# Struct.net
KiCad netlist of a schematic drawn in Altium Designer
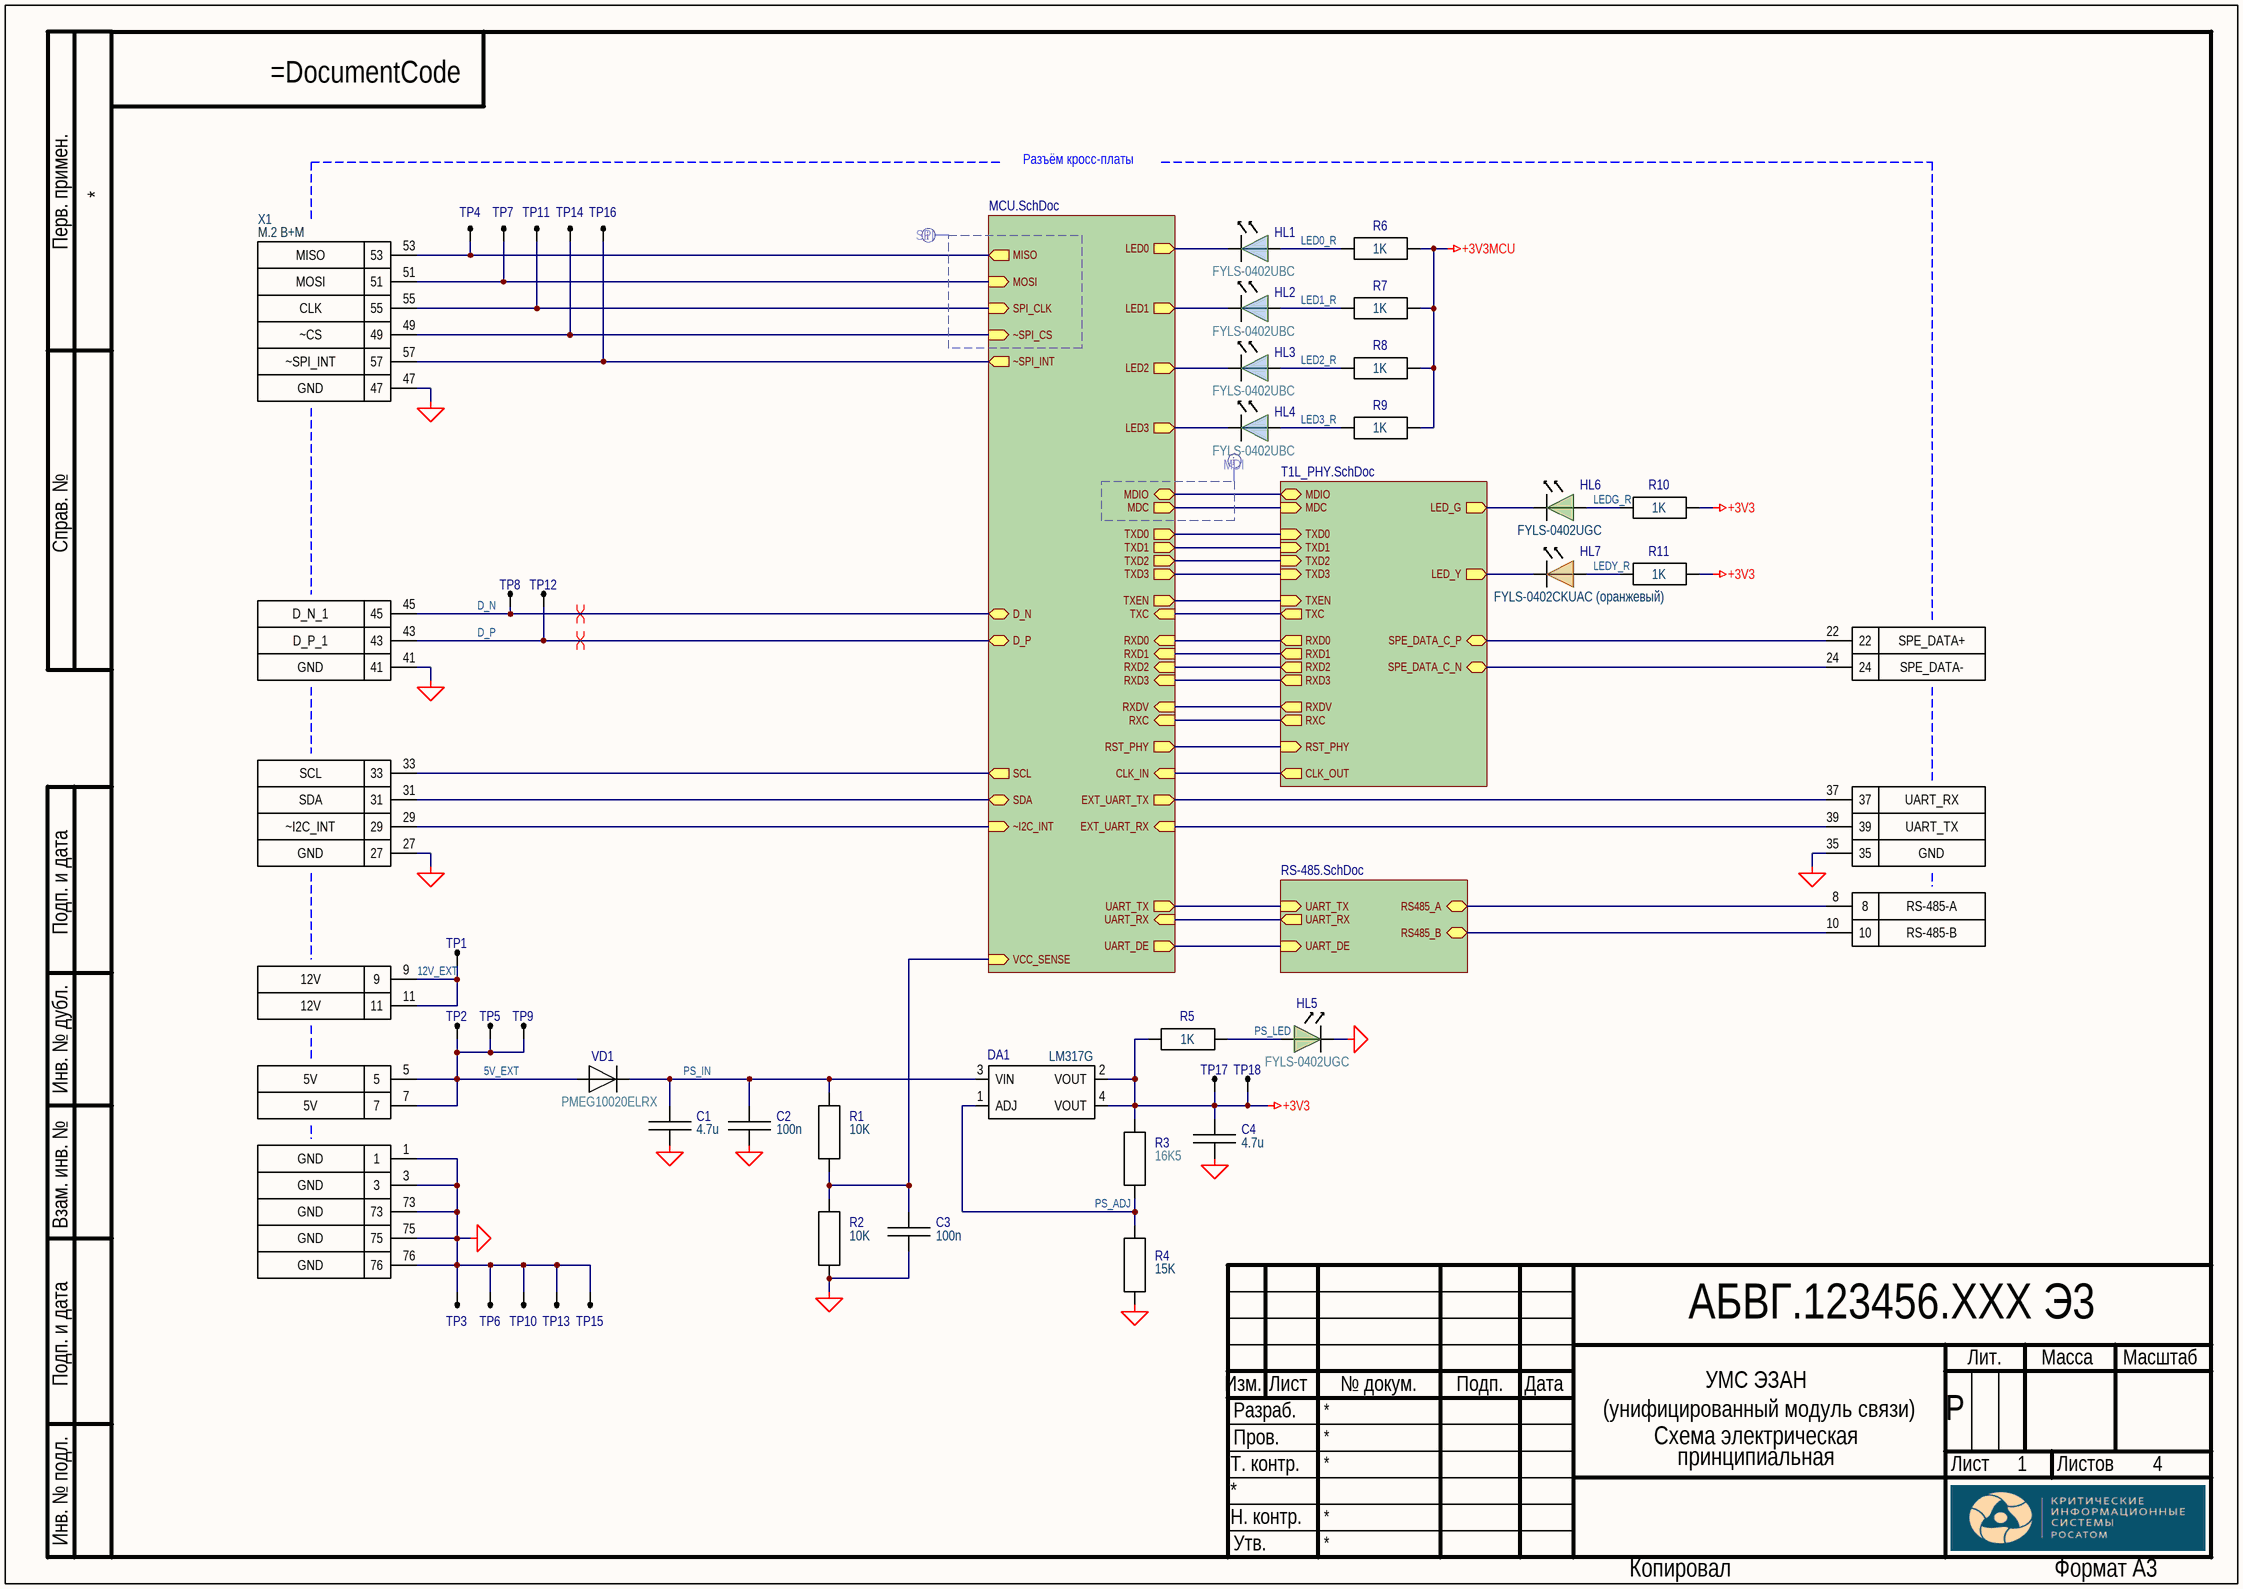
[diagram p0: Struct.SchDoc]

(export (version "E")
  (design (tool "Eeschema 10.0.6"))
  (components
    (comp (ref "C1")
      (value "4.7u")
      (footprint "C0603")
      (description "Чип-конденсатор 4,7 мкФ 10% 16 В X5R 0603")
      (fields
        (field (name "MANUFACTURER PART NUMBER") "CC0603KRX5R7BB475")
        (field (name "MANUFACTURER") "Yageo")
      )
      (libsource (lib "ums") (part "C0603"))
    )
    (comp (ref "C2")
      (value "100n")
      (footprint "C0402")
      (description "Чип-конденсатор 100 нФ 10% 50 В X7R 0402")
      (fields
        (field (name "MANUFACTURER PART NUMBER") "CC0402KRX7R9BB104")
        (field (name "MANUFACTURER") "Yageo")
      )
      (libsource (lib "ums") (part "C0402"))
    )
    (comp (ref "C3")
      (value "100n")
      (footprint "C0402")
      (description "Чип-конденсатор 100 нФ 10% 50 В X7R 0402")
      (fields
        (field (name "MANUFACTURER PART NUMBER") "CC0402KRX7R9BB104")
        (field (name "MANUFACTURER") "Yageo")
      )
      (libsource (lib "ums") (part "C0402"))
    )
    (comp (ref "C4")
      (value "4.7u")
      (footprint "C0603")
      (description "Чип-конденсатор 4,7 мкФ 10% 16 В X5R 0603")
      (fields
        (field (name "MANUFACTURER PART NUMBER") "CC0603KRX5R7BB475")
        (field (name "MANUFACTURER") "Yageo")
      )
      (libsource (lib "ums") (part "C0603"))
    )
    (comp (ref "DA1")
      (value "LM317G")
      (footprint "SOT-223")
      (description "LDO-регулятор SOT-223")
      (fields (field (name "MANUFACTURER") "UMW"))
      (libsource (lib "mconv_fnr_eval_v1") (part "LM317G"))
    )
    (comp (ref "HL1")
      (value "FYLS-0402UBC")
      (footprint "LED_SMD_0402_blue")
      (description "Светодиод SMD 0402 прямой синий FYLS-0402UBC")
      (fields (field (name "MANUFACTURER") "Foryard"))
      (libsource (lib "ums") (part "FYLS-0402UBC"))
    )
    (comp (ref "HL2")
      (value "FYLS-0402UBC")
      (footprint "LED_SMD_0402_blue")
      (description "Светодиод SMD 0402 прямой синий FYLS-0402UBC")
      (fields (field (name "MANUFACTURER") "Foryard"))
      (libsource (lib "ums") (part "FYLS-0402UBC"))
    )
    (comp (ref "HL3")
      (value "FYLS-0402UBC")
      (footprint "LED_SMD_0402_blue")
      (description "Светодиод SMD 0402 прямой синий FYLS-0402UBC")
      (fields (field (name "MANUFACTURER") "Foryard"))
      (libsource (lib "ums") (part "FYLS-0402UBC"))
    )
    (comp (ref "HL4")
      (value "FYLS-0402UBC")
      (footprint "LED_SMD_0402_blue")
      (description "Светодиод SMD 0402 прямой синий FYLS-0402UBC")
      (fields (field (name "MANUFACTURER") "Foryard"))
      (libsource (lib "ums") (part "FYLS-0402UBC"))
    )
    (comp (ref "HL5")
      (value "FYLS-0402UGC")
      (footprint "LED_SMD_0402")
      (description "Светодиод SMD 0402 прямой зелёный FYLS-0402UGC")
      (fields (field (name "MANUFACTURER") "Foryard"))
      (libsource (lib "ums") (part "FYLS-0402UGC"))
    )
    (comp (ref "HL6")
      (value "FYLS-0402UGC")
      (footprint "LED_SMD_0402")
      (description "Светодиод SMD 0402 прямой зелёный FYLS-0402UGC")
      (fields (field (name "MANUFACTURER") "Foryard"))
      (libsource (lib "ums") (part "FYLS-0402UGC"))
    )
    (comp (ref "HL7")
      (value "FYLS-0402CKUAC (оранжевый)")
      (footprint "LED_SMD_0402_orange")
      (description "Светодиод SMD 0402 прямой оранжевый 0402")
      (fields
        (field (name "MANUFACTURER PART NUMBER") "FYLS-0402CKUAC")
        (field (name "MANUFACTURER") "Foryard")
      )
      (libsource (lib "ums") (part "FYLS-0402CKUAC"))
    )
    (comp (ref "R1")
      (value "10K")
      (footprint "R0402")
      (description "Чип-резистор 10 кОм 1% 0402")
      (fields
        (field (name "MANUFACTURER PART NUMBER") "RC0402FR-0710KL")
        (field (name "MANUFACTURER") "Yageo")
      )
      (libsource (lib "ums") (part "R0402_1"))
    )
    (comp (ref "R2")
      (value "10K")
      (footprint "R0402")
      (description "Чип-резистор 10 кОм 1% 0402")
      (fields
        (field (name "MANUFACTURER PART NUMBER") "RC0402FR-0710KL")
        (field (name "MANUFACTURER") "Yageo")
      )
      (libsource (lib "ums") (part "R0402_1"))
    )
    (comp (ref "R3")
      (value "16K5")
      (footprint "R0603")
      (description "Чип-резистор 16,5 кОм 1% 0603")
      (fields
        (field (name "MANUFACTURER PART NUMBER") "RC0603FR-0716K5L")
        (field (name "MANUFACTURER") "Yageo")
      )
      (libsource (lib "ums") (part "R0603_3"))
    )
    (comp (ref "R4")
      (value "15K")
      (footprint "R0603")
      (description "Чип-резистор 15 кОм 1% 0603")
      (fields
        (field (name "MANUFACTURER PART NUMBER") "RC0603FR-0715KL")
        (field (name "MANUFACTURER") "Yageo")
      )
      (libsource (lib "mconv_fnr_eval_v1") (part "R0603_23"))
    )
    (comp (ref "R5")
      (value "1K")
      (footprint "R0402")
      (description "Чип-резистор 1 кОм 1% 0402")
      (fields
        (field (name "MANUFACTURER PART NUMBER") "RC0402FR-071KL")
        (field (name "MANUFACTURER") "Yageo")
      )
      (libsource (lib "ums") (part "R0402_4"))
    )
    (comp (ref "R6")
      (value "1K")
      (footprint "R0402")
      (description "Чип-резистор 1 кОм 1% 0402")
      (fields
        (field (name "MANUFACTURER PART NUMBER") "RC0402FR-071KL")
        (field (name "MANUFACTURER") "Yageo")
      )
      (libsource (lib "ums") (part "R0402_4"))
    )
    (comp (ref "R7")
      (value "1K")
      (footprint "R0402")
      (description "Чип-резистор 1 кОм 1% 0402")
      (fields
        (field (name "MANUFACTURER PART NUMBER") "RC0402FR-071KL")
        (field (name "MANUFACTURER") "Yageo")
      )
      (libsource (lib "ums") (part "R0402_4"))
    )
    (comp (ref "R8")
      (value "1K")
      (footprint "R0402")
      (description "Чип-резистор 1 кОм 1% 0402")
      (fields
        (field (name "MANUFACTURER PART NUMBER") "RC0402FR-071KL")
        (field (name "MANUFACTURER") "Yageo")
      )
      (libsource (lib "ums") (part "R0402_4"))
    )
    (comp (ref "R9")
      (value "1K")
      (footprint "R0402")
      (description "Чип-резистор 1 кОм 1% 0402")
      (fields
        (field (name "MANUFACTURER PART NUMBER") "RC0402FR-071KL")
        (field (name "MANUFACTURER") "Yageo")
      )
      (libsource (lib "ums") (part "R0402_4"))
    )
    (comp (ref "R10")
      (value "1K")
      (footprint "R0402")
      (description "Чип-резистор 1 кОм 1% 0402")
      (fields
        (field (name "MANUFACTURER PART NUMBER") "RC0402FR-071KL")
        (field (name "MANUFACTURER") "Yageo")
      )
      (libsource (lib "ums") (part "R0402_4"))
    )
    (comp (ref "R11")
      (value "1K")
      (footprint "R0402")
      (description "Чип-резистор 1 кОм 1% 0402")
      (fields
        (field (name "MANUFACTURER PART NUMBER") "RC0402FR-071KL")
        (field (name "MANUFACTURER") "Yageo")
      )
      (libsource (lib "ums") (part "R0402_4"))
    )
    (comp (ref "TP1")
      (value "TEST_POINT_SMD")
      (footprint "TEST_POINT_SMD")
      (description "Контрольная точка SMD")
      (libsource (lib "ums") (part "TEST_POINT_SMD"))
    )
    (comp (ref "TP2")
      (value "TEST_POINT_SMD")
      (footprint "TEST_POINT_SMD")
      (description "Контрольная точка SMD")
      (libsource (lib "ums") (part "TEST_POINT_SMD"))
    )
    (comp (ref "TP3")
      (value "TEST_POINT_1.27_STEP")
      (footprint "TEST_POINT_1.27_STEP")
      (description "Контрольная точка SMD")
      (libsource (lib "ums") (part "TEST_POINT_1.27_STEP"))
    )
    (comp (ref "TP4")
      (value "TEST_POINT_1.27_STEP")
      (footprint "TEST_POINT_1.27_STEP")
      (description "Контрольная точка SMD")
      (libsource (lib "ums") (part "TEST_POINT_1.27_STEP"))
    )
    (comp (ref "TP5")
      (value "TEST_POINT_1.27_STEP")
      (footprint "TEST_POINT_1.27_STEP")
      (description "Контрольная точка SMD")
      (libsource (lib "ums") (part "TEST_POINT_1.27_STEP"))
    )
    (comp (ref "TP6")
      (value "TEST_POINT_1.27_STEP")
      (footprint "TEST_POINT_1.27_STEP")
      (description "Контрольная точка SMD")
      (libsource (lib "ums") (part "TEST_POINT_1.27_STEP"))
    )
    (comp (ref "TP7")
      (value "TEST_POINT_1.27_STEP")
      (footprint "TEST_POINT_1.27_STEP")
      (description "Контрольная точка SMD")
      (libsource (lib "ums") (part "TEST_POINT_1.27_STEP"))
    )
    (comp (ref "TP8")
      (value "TEST_POINT_1.27_STEP")
      (footprint "TEST_POINT_1.27_STEP")
      (description "Контрольная точка SMD")
      (libsource (lib "ums") (part "TEST_POINT_1.27_STEP"))
    )
    (comp (ref "TP9")
      (value "TEST_POINT_1.27_STEP")
      (footprint "TEST_POINT_1.27_STEP")
      (description "Контрольная точка SMD")
      (libsource (lib "ums") (part "TEST_POINT_1.27_STEP"))
    )
    (comp (ref "TP10")
      (value "TEST_POINT_SMD")
      (footprint "TEST_POINT_SMD")
      (description "Контрольная точка SMD")
      (libsource (lib "ums") (part "TEST_POINT_SMD"))
    )
    (comp (ref "TP11")
      (value "TEST_POINT_1.27_STEP")
      (footprint "TEST_POINT_1.27_STEP")
      (description "Контрольная точка SMD")
      (libsource (lib "ums") (part "TEST_POINT_1.27_STEP"))
    )
    (comp (ref "TP12")
      (value "TEST_POINT_1.27_STEP")
      (footprint "TEST_POINT_1.27_STEP")
      (description "Контрольная точка SMD")
      (libsource (lib "ums") (part "TEST_POINT_1.27_STEP"))
    )
    (comp (ref "TP13")
      (value "TEST_POINT_1.27_STEP")
      (footprint "TEST_POINT_1.27_STEP")
      (description "Контрольная точка SMD")
      (libsource (lib "ums") (part "TEST_POINT_1.27_STEP"))
    )
    (comp (ref "TP14")
      (value "TEST_POINT_1.27_STEP")
      (footprint "TEST_POINT_1.27_STEP")
      (description "Контрольная точка SMD")
      (libsource (lib "ums") (part "TEST_POINT_1.27_STEP"))
    )
    (comp (ref "TP15")
      (value "TEST_POINT_1.27_STEP")
      (footprint "TEST_POINT_1.27_STEP")
      (description "Контрольная точка SMD")
      (libsource (lib "ums") (part "TEST_POINT_1.27_STEP"))
    )
    (comp (ref "TP16")
      (value "TEST_POINT_1.27_STEP")
      (footprint "TEST_POINT_1.27_STEP")
      (description "Контрольная точка SMD")
      (libsource (lib "ums") (part "TEST_POINT_1.27_STEP"))
    )
    (comp (ref "TP17")
      (value "TEST_POINT_1.27_STEP")
      (footprint "TEST_POINT_1.27_STEP")
      (description "Контрольная точка SMD")
      (libsource (lib "ums") (part "TEST_POINT_1.27_STEP"))
    )
    (comp (ref "TP18")
      (value "TEST_POINT_1.27_STEP")
      (footprint "TEST_POINT_1.27_STEP")
      (description "Контрольная точка SMD")
      (libsource (lib "ums") (part "TEST_POINT_1.27_STEP"))
    )
    (comp (ref "VD1")
      (value "PMEG10020ELRX")
      (footprint "SOD123W")
      (description "Диод Шоттки SOD123W")
      (fields (field (name "MANUFACTURER") "Nexperia"))
      (libsource (lib "ums") (part "PMEG10020ELRX"))
    )
    (comp (ref "X1")
      (value "M2_3030_M_Partial")
      (footprint "m2-3030-B+M")
      (libsource (lib "ums") (part "M2_3030_B+M_Partial"))
    )
  )
  (nets
    (net (code "1") (name "+3V3") (class "Default")
      (node (ref "C4") (pin "1") (pinfunction "1_1") (pintype "passive"))
      (node (ref "DA1") (pin "2") (pinfunction "VOUT_2") (pintype "passive"))
      (node (ref "DA1") (pin "4") (pinfunction "VOUT_4") (pintype "passive"))
      (node (ref "R10") (pin "2") (pinfunction "2_2") (pintype "passive"))
      (node (ref "R11") (pin "2") (pinfunction "2_2") (pintype "passive"))
      (node (ref "R3") (pin "2") (pinfunction "2_2") (pintype "passive"))
      (node (ref "R5") (pin "1") (pinfunction "1_1") (pintype "passive"))
      (node (ref "TP17") (pin "1") (pinfunction "1_1") (pintype "passive"))
      (node (ref "TP18") (pin "1") (pinfunction "1_1") (pintype "passive"))
    )
    (net (code "2") (name "+3V3MCU") (class "Default")
      (node (ref "R6") (pin "2") (pinfunction "2_2") (pintype "passive"))
      (node (ref "R7") (pin "2") (pinfunction "2_2") (pintype "passive"))
      (node (ref "R8") (pin "2") (pinfunction "2_2") (pintype "passive"))
      (node (ref "R9") (pin "2") (pinfunction "2_2") (pintype "passive"))
    )
    (net (code "3") (name "/5V_EXT") (class "Default")
      (node (ref "TP2") (pin "1") (pinfunction "1_1") (pintype "passive"))
      (node (ref "TP5") (pin "1") (pinfunction "1_1") (pintype "passive"))
      (node (ref "TP9") (pin "1") (pinfunction "1_1") (pintype "passive"))
      (node (ref "VD1") (pin "2") (pinfunction "2_2") (pintype "passive"))
      (node (ref "X1") (pin "5") (pinfunction "5_5") (pintype "passive"))
      (node (ref "X1") (pin "7") (pinfunction "7_7") (pintype "passive"))
    )
    (net (code "4") (name "/12V_EXT") (class "Default")
      (node (ref "TP1") (pin "1") (pinfunction "1_1") (pintype "passive"))
      (node (ref "X1") (pin "11") (pinfunction "11_11") (pintype "passive"))
      (node (ref "X1") (pin "9") (pinfunction "9_9") (pintype "passive"))
    )
    (net (code "7") (name "/D_N") (class "Default")
      (node (ref "TP8") (pin "1") (pinfunction "1_1") (pintype "passive"))
      (node (ref "X1") (pin "45") (pinfunction "45_45") (pintype "passive"))
    )
    (net (code "8") (name "/D_P") (class "Default")
      (node (ref "TP12") (pin "1") (pinfunction "1_1") (pintype "passive"))
      (node (ref "X1") (pin "43") (pinfunction "43_43") (pintype "passive"))
    )
    (net (code "9") (name "/EXT_UART_RX") (class "Default")
      (node (ref "X1") (pin "39") (pinfunction "39_39") (pintype "passive"))
    )
    (net (code "10") (name "/EXT_UART_TX") (class "Default")
      (node (ref "X1") (pin "37") (pinfunction "37_37") (pintype "passive"))
    )
    (net (code "11") (name "/LED0") (class "Default")
      (node (ref "HL1") (pin "2") (pinfunction "2_2") (pintype "passive"))
    )
    (net (code "12") (name "/LED0_R") (class "Default")
      (node (ref "HL1") (pin "1") (pinfunction "1_1") (pintype "passive"))
      (node (ref "R6") (pin "1") (pinfunction "1_1") (pintype "passive"))
    )
    (net (code "13") (name "/LED1") (class "Default")
      (node (ref "HL2") (pin "2") (pinfunction "2_2") (pintype "passive"))
    )
    (net (code "14") (name "/LED1_R") (class "Default")
      (node (ref "HL2") (pin "1") (pinfunction "1_1") (pintype "passive"))
      (node (ref "R7") (pin "1") (pinfunction "1_1") (pintype "passive"))
    )
    (net (code "15") (name "/LED2") (class "Default")
      (node (ref "HL3") (pin "2") (pinfunction "2_2") (pintype "passive"))
    )
    (net (code "16") (name "/LED2_R") (class "Default")
      (node (ref "HL3") (pin "1") (pinfunction "1_1") (pintype "passive"))
      (node (ref "R8") (pin "1") (pinfunction "1_1") (pintype "passive"))
    )
    (net (code "17") (name "/LED3") (class "Default")
      (node (ref "HL4") (pin "2") (pinfunction "2_2") (pintype "passive"))
    )
    (net (code "18") (name "/LED3_R") (class "Default")
      (node (ref "HL4") (pin "1") (pinfunction "1_1") (pintype "passive"))
      (node (ref "R9") (pin "1") (pinfunction "1_1") (pintype "passive"))
    )
    (net (code "19") (name "/LEDG_R") (class "Default")
      (node (ref "HL6") (pin "1") (pinfunction "1_1") (pintype "passive"))
      (node (ref "R10") (pin "1") (pinfunction "1_1") (pintype "passive"))
    )
    (net (code "20") (name "/LEDY_R") (class "Default")
      (node (ref "HL7") (pin "1") (pinfunction "1_1") (pintype "passive"))
      (node (ref "R11") (pin "1") (pinfunction "1_1") (pintype "passive"))
    )
    (net (code "21") (name "/LED_G") (class "Default")
      (node (ref "HL6") (pin "2") (pinfunction "2_2") (pintype "passive"))
    )
    (net (code "22") (name "/LED_Y") (class "Default")
      (node (ref "HL7") (pin "2") (pinfunction "2_2") (pintype "passive"))
    )
    (net (code "25") (name "/MISO") (class "Default")
      (node (ref "TP4") (pin "1") (pinfunction "1_1") (pintype "passive"))
      (node (ref "X1") (pin "53") (pinfunction "53_53") (pintype "passive"))
    )
    (net (code "26") (name "/MOSI") (class "Default")
      (node (ref "TP7") (pin "1") (pinfunction "1_1") (pintype "passive"))
      (node (ref "X1") (pin "51") (pinfunction "51_51") (pintype "passive"))
    )
    (net (code "27") (name "/PS_ADJ") (class "Default")
      (node (ref "DA1") (pin "1") (pinfunction "ADJ_1") (pintype "passive"))
      (node (ref "R3") (pin "1") (pinfunction "1_1") (pintype "passive"))
      (node (ref "R4") (pin "2") (pinfunction "2_2") (pintype "passive"))
    )
    (net (code "28") (name "/PS_IN") (class "Default")
      (node (ref "C1") (pin "1") (pinfunction "1_1") (pintype "passive"))
      (node (ref "C2") (pin "2") (pinfunction "2_2") (pintype "passive"))
      (node (ref "DA1") (pin "3") (pinfunction "VIN_3") (pintype "passive"))
      (node (ref "R1") (pin "2") (pinfunction "2_2") (pintype "passive"))
      (node (ref "VD1") (pin "1") (pinfunction "1_1") (pintype "passive"))
    )
    (net (code "29") (name "/PS_LED") (class "Default")
      (node (ref "HL5") (pin "1") (pinfunction "1_1") (pintype "passive"))
      (node (ref "R5") (pin "2") (pinfunction "2_2") (pintype "passive"))
    )
    (net (code "30") (name "/RS485_A") (class "Default")
      (node (ref "X1") (pin "8") (pinfunction "8_8") (pintype "passive"))
    )
    (net (code "31") (name "/RS485_B") (class "Default")
      (node (ref "X1") (pin "10") (pinfunction "10_10") (pintype "passive"))
    )
    (net (code "39") (name "/SCL") (class "Default")
      (node (ref "X1") (pin "33") (pinfunction "33_33") (pintype "passive"))
    )
    (net (code "40") (name "/SDA") (class "Default")
      (node (ref "X1") (pin "31") (pinfunction "31_31") (pintype "passive"))
    )
    (net (code "41") (name "/SPE_DATA_C_N") (class "Default")
      (node (ref "X1") (pin "24") (pinfunction "24_24") (pintype "passive"))
    )
    (net (code "42") (name "/SPE_DATA_C_P") (class "Default")
      (node (ref "X1") (pin "22") (pinfunction "22_22") (pintype "passive"))
    )
    (net (code "43") (name "/SPI_CLK") (class "Default")
      (node (ref "TP11") (pin "1") (pinfunction "1_1") (pintype "passive"))
      (node (ref "X1") (pin "55") (pinfunction "5_55") (pintype "passive"))
    )
    (net (code "53") (name "/VCC_SENSE") (class "Default")
      (node (ref "C3") (pin "2") (pinfunction "2_2") (pintype "passive"))
      (node (ref "R1") (pin "1") (pinfunction "1_1") (pintype "passive"))
      (node (ref "R2") (pin "2") (pinfunction "2_2") (pintype "passive"))
    )
    (net (code "54") (name "/~I2C_INT") (class "Default")
      (node (ref "X1") (pin "29") (pinfunction "29_29") (pintype "passive"))
    )
    (net (code "55") (name "/~SPI_CS") (class "Default")
      (node (ref "TP14") (pin "1") (pinfunction "1_1") (pintype "passive"))
      (node (ref "X1") (pin "49") (pinfunction "49_49") (pintype "passive"))
    )
    (net (code "56") (name "/~SPI_INT") (class "Default")
      (node (ref "TP16") (pin "1") (pinfunction "1_1") (pintype "passive"))
      (node (ref "X1") (pin "57") (pinfunction "57_57") (pintype "passive"))
    )
    (net (code "57") (name "GND") (class "Default")
      (node (ref "C1") (pin "2") (pinfunction "2_2") (pintype "passive"))
      (node (ref "C2") (pin "1") (pinfunction "1_1") (pintype "passive"))
      (node (ref "C3") (pin "1") (pinfunction "1_1") (pintype "passive"))
      (node (ref "C4") (pin "2") (pinfunction "2_2") (pintype "passive"))
      (node (ref "HL5") (pin "2") (pinfunction "2_2") (pintype "passive"))
      (node (ref "R2") (pin "1") (pinfunction "1_1") (pintype "passive"))
      (node (ref "R4") (pin "1") (pinfunction "1_1") (pintype "passive"))
      (node (ref "TP10") (pin "1") (pinfunction "1_1") (pintype "passive"))
      (node (ref "TP13") (pin "1") (pinfunction "1_1") (pintype "passive"))
      (node (ref "TP15") (pin "1") (pinfunction "1_1") (pintype "passive"))
      (node (ref "TP3") (pin "1") (pinfunction "1_1") (pintype "passive"))
      (node (ref "TP6") (pin "1") (pinfunction "1_1") (pintype "passive"))
      (node (ref "X1") (pin "1") (pinfunction "1_1") (pintype "passive"))
      (node (ref "X1") (pin "27") (pinfunction "27_27") (pintype "passive"))
      (node (ref "X1") (pin "3") (pinfunction "3_3") (pintype "passive"))
      (node (ref "X1") (pin "35") (pinfunction "35_35") (pintype "passive"))
      (node (ref "X1") (pin "41") (pinfunction "41_41") (pintype "passive"))
      (node (ref "X1") (pin "47") (pinfunction "47_47") (pintype "passive"))
      (node (ref "X1") (pin "73") (pinfunction "73_73") (pintype "passive"))
      (node (ref "X1") (pin "75") (pinfunction "75_75") (pintype "passive"))
      (node (ref "X1") (pin "76") (pinfunction "76_76") (pintype "passive"))
    )
  )
)
